# ACCUM-SIGNAL.net
KiCad netlist of a schematic drawn in EAGLE
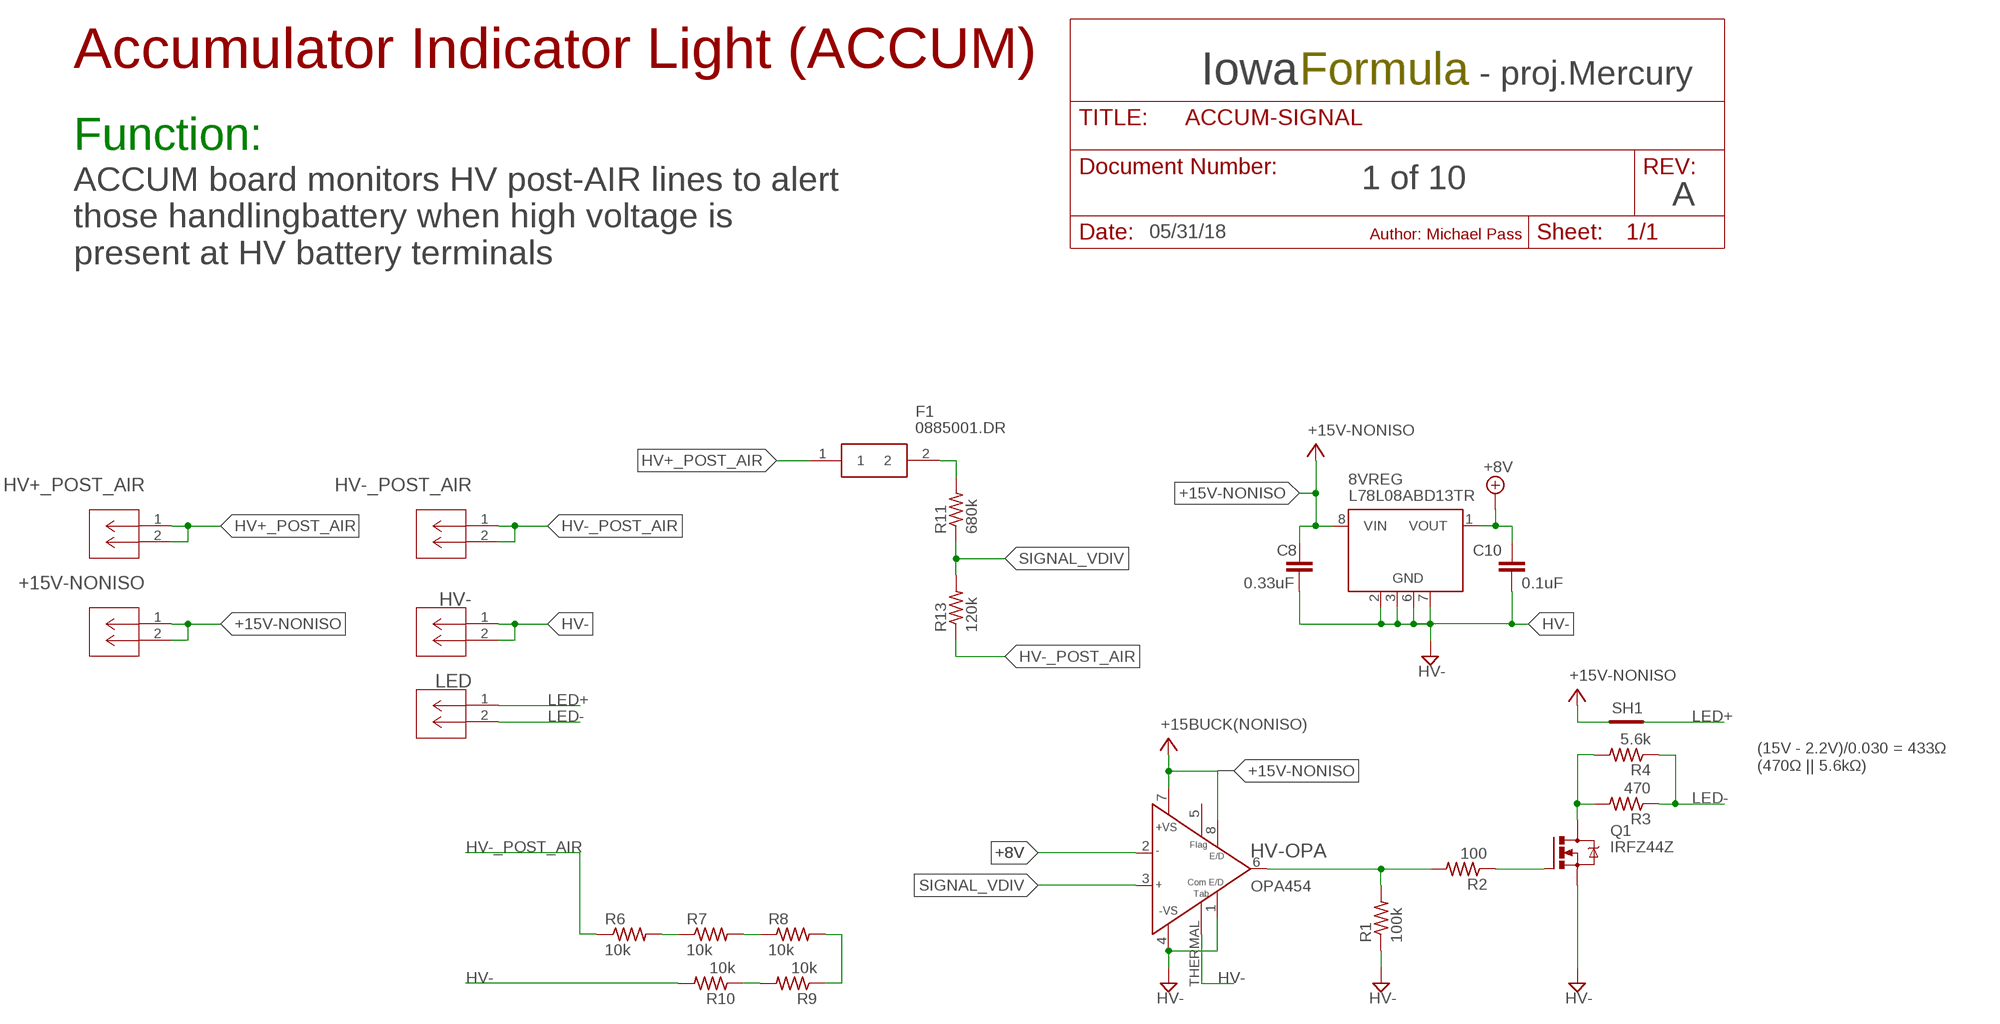
[diagram p0: schematic, sheet 1]

(export (version "E")
  (design (tool "Eeschema 10.0.6"))
  (components
    (comp (ref "+15V-NONISO")
      (value "2P(90DEG)_1-770966-0")
      (footprint "eagle-import:CON2_1X2_P163_RAMNL")
      (fields (field (name "MANUFACTURER_PART_NUMBER") "17709660"))
      (libsource (lib "eagle-import") (part "2P(90DEG)_1-770966-0"))
    )
    (comp (ref "8VREG")
      (value "L78L08ABD13TR")
      (footprint "eagle-import:SO08")
      (libsource (lib "eagle-import") (part "78LSMD08"))
    )
    (comp (ref "C8")
      (value "0.33uF")
      (footprint "eagle-import:C0805")
      (libsource (lib "eagle-import") (part "C-EUC0805"))
    )
    (comp (ref "C10")
      (value "0.1uF")
      (footprint "eagle-import:C0805")
      (libsource (lib "eagle-import") (part "C-EUC0805"))
    )
    (comp (ref "F1")
      (value "0885001.DR")
      (footprint "eagle-import:FUSC10948X488N")
      (fields (field (name "MOUSER_PART_NUMBER") "576-0885001.DR"))
      (libsource (lib "eagle-import") (part "0885001.DR"))
    )
    (comp (ref "HV+_POST_AIR")
      (value "2P(90DEG)_1-770966-0")
      (footprint "eagle-import:CON2_1X2_P163_RAMNL")
      (fields (field (name "MANUFACTURER_PART_NUMBER") "17709660"))
      (libsource (lib "eagle-import") (part "2P(90DEG)_1-770966-0"))
    )
    (comp (ref "HV-")
      (value "2P(90DEG)_1-770966-0")
      (footprint "eagle-import:CON2_1X2_P163_RAMNL")
      (fields (field (name "MANUFACTURER_PART_NUMBER") "17709660"))
      (libsource (lib "eagle-import") (part "2P(90DEG)_1-770966-0"))
    )
    (comp (ref "HV-OPA")
      (value "OPA454")
      (footprint "eagle-import:SO08GP")
      (fields (field (name "MF") "Texas Instruments"))
      (libsource (lib "eagle-import") (part "OPA454"))
    )
    (comp (ref "HV-_POST_AIR")
      (value "2P(90DEG)_1-770966-0")
      (footprint "eagle-import:CON2_1X2_P163_RAMNL")
      (fields (field (name "MANUFACTURER_PART_NUMBER") "17709660"))
      (libsource (lib "eagle-import") (part "2P(90DEG)_1-770966-0"))
    )
    (comp (ref "LED")
      (value "2P(90DEG)_1-770966-0")
      (footprint "eagle-import:CON2_1X2_P163_RAMNL")
      (fields (field (name "MANUFACTURER_PART_NUMBER") "17709660"))
      (libsource (lib "eagle-import") (part "2P(90DEG)_1-770966-0"))
    )
    (comp (ref "Q1")
      (value "IRFZ44Z")
      (footprint "eagle-import:TO220BH")
      (libsource (lib "eagle-import") (part "IRLZ44Z"))
    )
    (comp (ref "R1")
      (value "100k")
      (footprint "eagle-import:R0805")
      (libsource (lib "eagle-import") (part "R-US_R0805"))
    )
    (comp (ref "R2")
      (value "100")
      (footprint "eagle-import:R0805")
      (libsource (lib "eagle-import") (part "R-US_R0805"))
    )
    (comp (ref "R3")
      (value "470")
      (footprint "eagle-import:R0805")
      (libsource (lib "eagle-import") (part "R-US_R0805"))
    )
    (comp (ref "R4")
      (value "5.6k")
      (footprint "eagle-import:R0805")
      (libsource (lib "eagle-import") (part "R-US_R0805"))
    )
    (comp (ref "R6")
      (value "10k")
      (footprint "eagle-import:R0805")
      (libsource (lib "eagle-import") (part "R-US_R0805"))
    )
    (comp (ref "R7")
      (value "10k")
      (footprint "eagle-import:R0805")
      (libsource (lib "eagle-import") (part "R-US_R0805"))
    )
    (comp (ref "R8")
      (value "10k")
      (footprint "eagle-import:R0805")
      (libsource (lib "eagle-import") (part "R-US_R0805"))
    )
    (comp (ref "R9")
      (value "10k")
      (footprint "eagle-import:R0805")
      (libsource (lib "eagle-import") (part "R-US_R0805"))
    )
    (comp (ref "R10")
      (value "10k")
      (footprint "eagle-import:R0805")
      (libsource (lib "eagle-import") (part "R-US_R0805"))
    )
    (comp (ref "R11")
      (value "680k")
      (footprint "eagle-import:R0805")
      (libsource (lib "eagle-import") (part "R-US_R0805"))
    )
    (comp (ref "R13")
      (value "120k")
      (footprint "eagle-import:R0805")
      (libsource (lib "eagle-import") (part "R-US_R0805"))
    )
    (comp (ref "SH1")
      (value "SHORTT5")
      (footprint "eagle-import:SHORT_TOP-50")
      (libsource (lib "eagle-import") (part "SHORTT5"))
    )
  )
  (nets
    (net (code "1") (name "+8V") (class "Default")
      (node (ref "8VREG") (pin "1") (pinfunction "VOUT_1") (pintype "output"))
      (node (ref "C10") (pin "1") (pinfunction "1_1") (pintype "passive"))
      (node (ref "HV-OPA") (pin "2") (pinfunction "IN-_2") (pintype "input"))
    )
    (net (code "2") (name "+15V-NONISO") (class "Default")
      (node (ref "+15V-NONISO") (pin "1") (pinfunction "1_1") (pintype "passive"))
      (node (ref "+15V-NONISO") (pin "2") (pinfunction "2_2") (pintype "passive"))
      (node (ref "8VREG") (pin "8") (pinfunction "VIN_8") (pintype "passive"))
      (node (ref "C8") (pin "1") (pinfunction "1_1") (pintype "passive"))
      (node (ref "HV-OPA") (pin "7") (pinfunction "+VS_7") (pintype "passive"))
      (node (ref "HV-OPA") (pin "8") (pinfunction "E/D_8") (pintype "passive"))
      (node (ref "SH1") (pin "1") (pinfunction "P$1_1") (pintype "bidirectional"))
    )
    (net (code "3") (name "/LED+") (class "Default")
      (node (ref "LED") (pin "1") (pinfunction "1_1") (pintype "passive"))
      (node (ref "SH1") (pin "2") (pinfunction "P$2_2") (pintype "bidirectional"))
    )
    (net (code "4") (name "/LED-") (class "Default")
      (node (ref "LED") (pin "2") (pinfunction "2_2") (pintype "passive"))
      (node (ref "R3") (pin "1") (pinfunction "1_1") (pintype "passive"))
      (node (ref "R4") (pin "1") (pinfunction "1_1") (pintype "passive"))
    )
    (net (code "5") (name "HV+_POST_AIR") (class "Default")
      (node (ref "F1") (pin "1") (pinfunction "1_1") (pintype "bidirectional"))
      (node (ref "HV+_POST_AIR") (pin "1") (pinfunction "1_1") (pintype "passive"))
      (node (ref "HV+_POST_AIR") (pin "2") (pinfunction "2_2") (pintype "passive"))
    )
    (net (code "6") (name "HV-") (class "Default")
      (node (ref "8VREG") (pin "2") (pinfunction "GND_2") (pintype "power_in"))
      (node (ref "8VREG") (pin "3") (pinfunction "GND_3") (pintype "power_in"))
      (node (ref "8VREG") (pin "6") (pinfunction "GND_6") (pintype "power_in"))
      (node (ref "8VREG") (pin "7") (pinfunction "GND_7") (pintype "power_in"))
      (node (ref "C10") (pin "2") (pinfunction "2_2") (pintype "passive"))
      (node (ref "C8") (pin "2") (pinfunction "2_2") (pintype "passive"))
      (node (ref "HV-") (pin "1") (pinfunction "1_1") (pintype "passive"))
      (node (ref "HV-") (pin "2") (pinfunction "2_2") (pintype "passive"))
      (node (ref "HV-OPA") (pin "1") (pinfunction "E/DCOM_1") (pintype "passive"))
      (node (ref "HV-OPA") (pin "4") (pinfunction "-VS_4") (pintype "passive"))
      (node (ref "HV-OPA") (pin "THERMAL") (pinfunction "E/DCOM1_THERMAL") (pintype "passive"))
      (node (ref "Q1") (pin "S") (pinfunction "S_S") (pintype "passive"))
      (node (ref "R1") (pin "1") (pinfunction "1_1") (pintype "passive"))
      (node (ref "R10") (pin "2") (pinfunction "2_2") (pintype "passive"))
    )
    (net (code "7") (name "HV-_POST_AIR") (class "Default")
      (node (ref "HV-_POST_AIR") (pin "1") (pinfunction "1_1") (pintype "passive"))
      (node (ref "HV-_POST_AIR") (pin "2") (pinfunction "2_2") (pintype "passive"))
      (node (ref "R13") (pin "1") (pinfunction "1_1") (pintype "passive"))
      (node (ref "R6") (pin "1") (pinfunction "1_1") (pintype "passive"))
    )
    (net (code "8") (name "Net-(F1-Pad2)") (class "Default")
      (node (ref "F1") (pin "2") (pinfunction "2_2") (pintype "bidirectional"))
      (node (ref "R11") (pin "2") (pinfunction "2_2") (pintype "passive"))
    )
    (net (code "9") (name "Net-(HV-OPA-OUT)") (class "Default")
      (node (ref "HV-OPA") (pin "6") (pinfunction "OUT_6") (pintype "output"))
      (node (ref "R1") (pin "2") (pinfunction "2_2") (pintype "passive"))
      (node (ref "R2") (pin "2") (pinfunction "2_2") (pintype "passive"))
    )
    (net (code "10") (name "Net-(Q1-PadD)") (class "Default")
      (node (ref "Q1") (pin "D") (pinfunction "D_D") (pintype "passive"))
      (node (ref "R3") (pin "2") (pinfunction "2_2") (pintype "passive"))
      (node (ref "R4") (pin "2") (pinfunction "2_2") (pintype "passive"))
    )
    (net (code "11") (name "Net-(Q1-PadG)") (class "Default")
      (node (ref "Q1") (pin "G") (pinfunction "G_G") (pintype "passive"))
      (node (ref "R2") (pin "1") (pinfunction "1_1") (pintype "passive"))
    )
    (net (code "12") (name "Net-(R6-Pad2)") (class "Default")
      (node (ref "R6") (pin "2") (pinfunction "2_2") (pintype "passive"))
      (node (ref "R7") (pin "1") (pinfunction "1_1") (pintype "passive"))
    )
    (net (code "13") (name "Net-(R7-Pad2)") (class "Default")
      (node (ref "R7") (pin "2") (pinfunction "2_2") (pintype "passive"))
      (node (ref "R8") (pin "1") (pinfunction "1_1") (pintype "passive"))
    )
    (net (code "14") (name "Net-(R8-Pad2)") (class "Default")
      (node (ref "R8") (pin "2") (pinfunction "2_2") (pintype "passive"))
      (node (ref "R9") (pin "1") (pinfunction "1_1") (pintype "passive"))
    )
    (net (code "15") (name "Net-(R10-Pad1)") (class "Default")
      (node (ref "R10") (pin "1") (pinfunction "1_1") (pintype "passive"))
      (node (ref "R9") (pin "2") (pinfunction "2_2") (pintype "passive"))
    )
    (net (code "16") (name "SIGNAL_VDIV") (class "Default")
      (node (ref "HV-OPA") (pin "3") (pinfunction "IN+_3") (pintype "input"))
      (node (ref "R11") (pin "1") (pinfunction "1_1") (pintype "passive"))
      (node (ref "R13") (pin "2") (pinfunction "2_2") (pintype "passive"))
    )
    (net (code "17") (name "unconnected-(HV-OPA-STATUS-Pad5)") (class "Default")
      (node (ref "HV-OPA") (pin "5") (pinfunction "STATUS_5") (pintype "passive"))
    )
  )
)
